# mp28164-buck-boost-flashlight-driver-17m.net
KiCad netlist of a schematic drawn in EAGLE
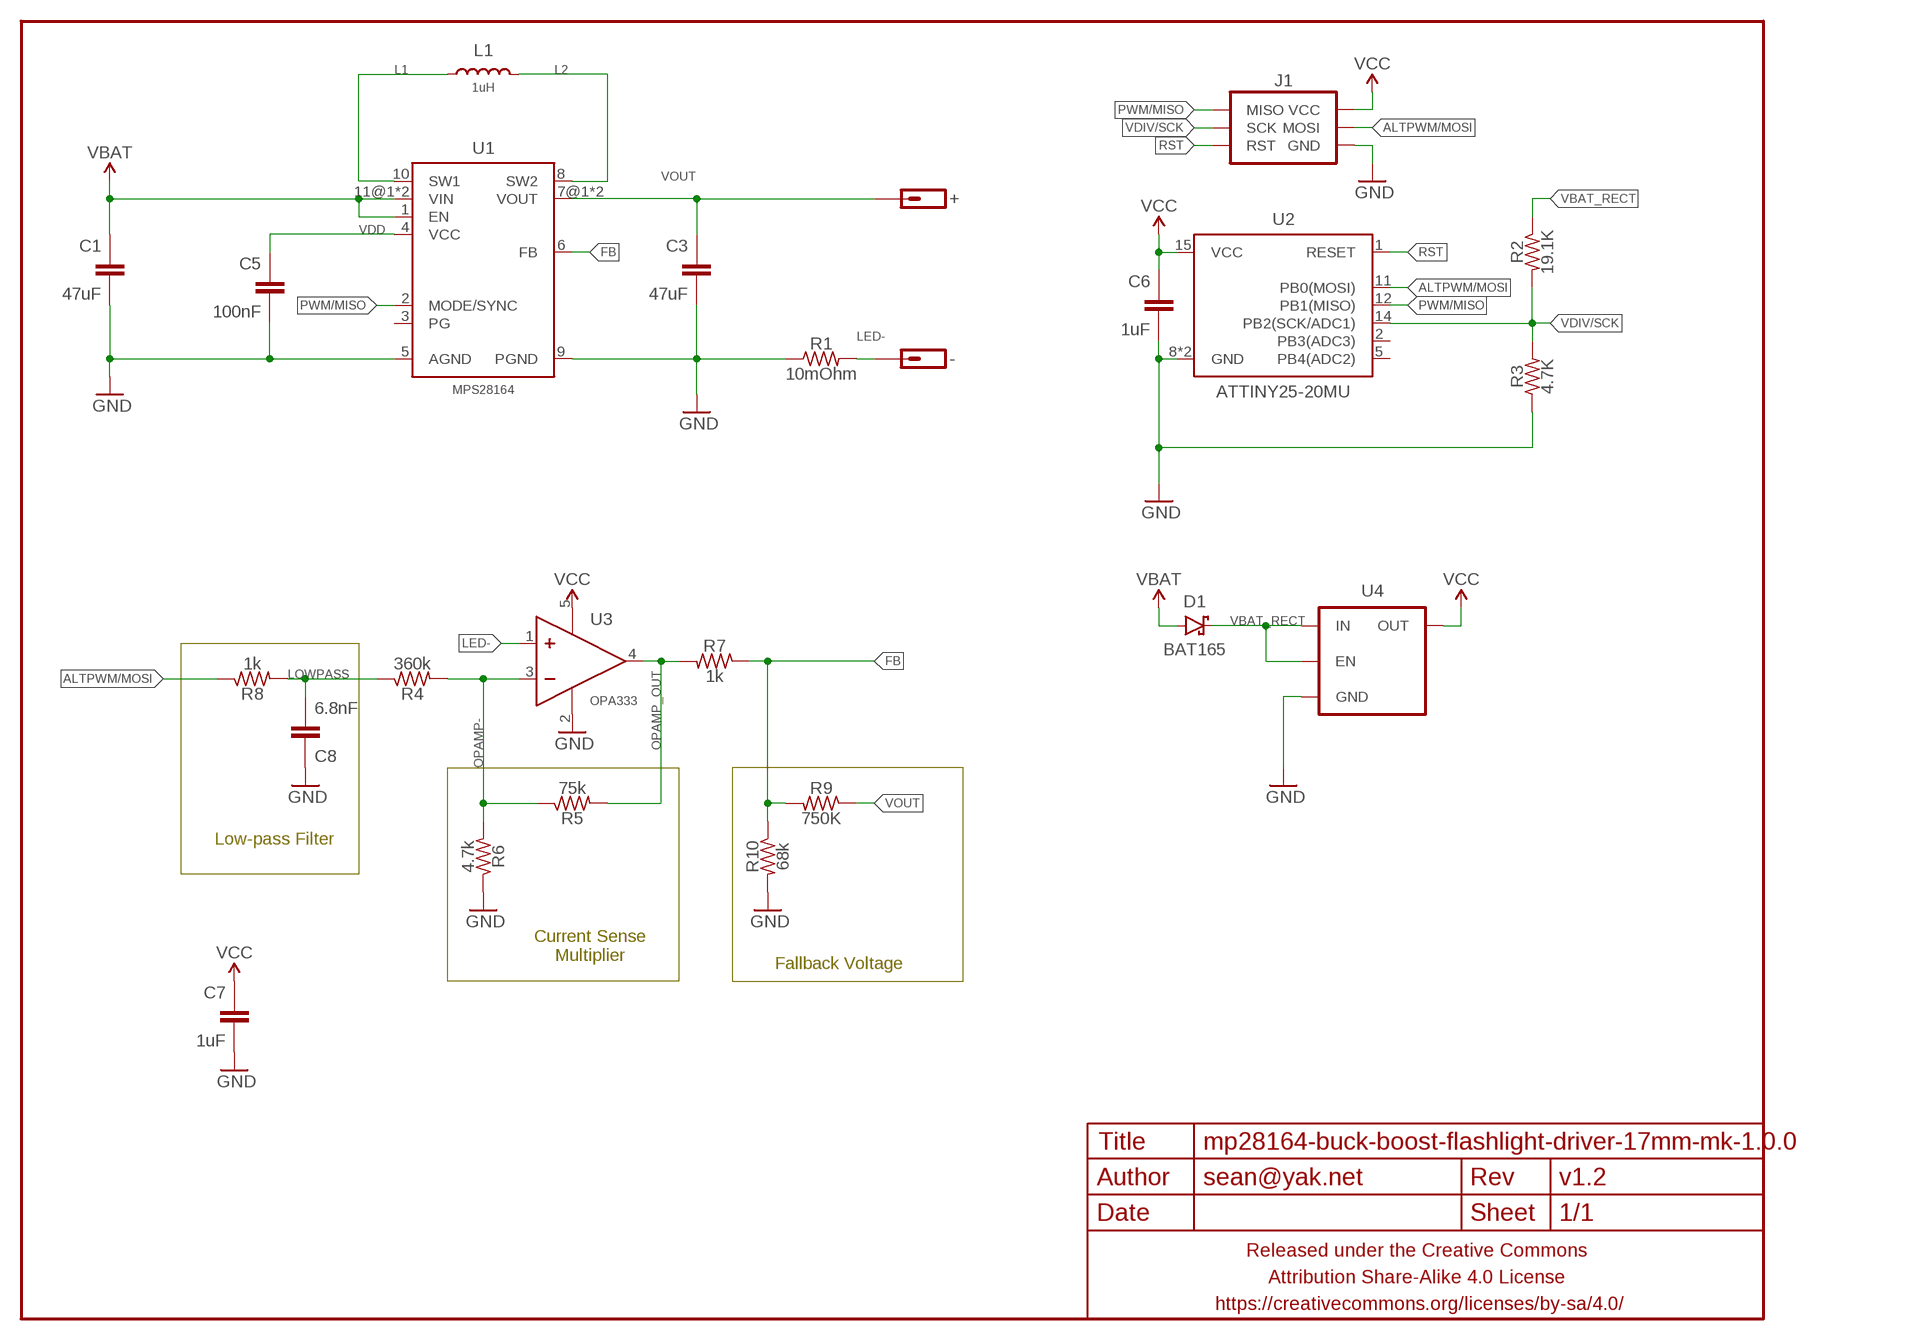
[diagram p0: schematic, sheet 1]

(export (version "E")
  (design (tool "Eeschema 10.0.6"))
  (components
    (comp (ref "+")
      (value "M01SMD-1.6MMX3.2MM-NS")
      (footprint "eagle-import:1X01-SMD-1.6MMX3.2MM-NS")
      (libsource (lib "eagle-import") (part "M01SMD-1.6MMX3.2MM-NS"))
    )
    (comp (ref "-")
      (value "M01SMD-1.6MMX3.2MM-NS")
      (footprint "eagle-import:1X01-SMD-1.6MMX3.2MM-NS")
      (libsource (lib "eagle-import") (part "M01SMD-1.6MMX3.2MM-NS"))
    )
    (comp (ref "C1")
      (value "47uF")
      (footprint "eagle-import:C1206")
      (libsource (lib "eagle-import") (part "CAPACITOR-CERAMICC1206"))
    )
    (comp (ref "C3")
      (value "47uF")
      (footprint "eagle-import:C1206")
      (libsource (lib "eagle-import") (part "CAPACITOR-CERAMICC1206"))
    )
    (comp (ref "C5")
      (value "100nF")
      (footprint "eagle-import:C0402")
      (libsource (lib "eagle-import") (part "CAPACITOR-CERAMICC0402"))
    )
    (comp (ref "C6")
      (value "1uF")
      (footprint "eagle-import:C0402")
      (libsource (lib "eagle-import") (part "CAPACITOR-CERAMICC0402"))
    )
    (comp (ref "C7")
      (value "1uF")
      (footprint "eagle-import:C0402")
      (libsource (lib "eagle-import") (part "CAPACITOR-CERAMICC0402"))
    )
    (comp (ref "C8")
      (value "6.8nF")
      (footprint "eagle-import:C0402")
      (libsource (lib "eagle-import") (part "CAPACITOR-CERAMICC0402"))
    )
    (comp (ref "D1")
      (value "BAT165")
      (footprint "eagle-import:SOD323-SCHOTTKY")
      (libsource (lib "eagle-import") (part "DIODE-SCHOTTKYSOD323"))
    )
    (comp (ref "FRAME1")
      (value "FRAME-LETTERNO_PACKAGE")
      (footprint "eagle-import:DUMMY")
      (fields
        (field (name "DESIGNER") "sean@yak.net")
        (field (name "VERSION") "v1.2")
        (field (name "DESIGNER_1") "sean@yak.net")
        (field (name "VERSION_1") "v1.2")
      )
      (libsource (lib "eagle-import") (part "FRAME-LETTERNO_PACKAGE"))
    )
    (comp (ref "J1")
      (value "AVR_SPI_PRG_6SMD-1.27MM")
      (footprint "eagle-import:2X3-1.27MM-SMD")
      (libsource (lib "eagle-import") (part "AVR_SPI_PRG_6SMD-1.27MM"))
    )
    (comp (ref "L1")
      (value "1uH")
      (footprint "eagle-import:XAL7070")
      (libsource (lib "eagle-import") (part "INDUCTORXAL7070"))
    )
    (comp (ref "R1")
      (value "10mOhm")
      (footprint "eagle-import:R0805-TIGHTER")
      (libsource (lib "eagle-import") (part "RESISTORR0805-TIGHTER"))
    )
    (comp (ref "R2")
      (value "19.1K")
      (footprint "eagle-import:R0402")
      (libsource (lib "eagle-import") (part "RESISTORR0402"))
    )
    (comp (ref "R3")
      (value "4.7K")
      (footprint "eagle-import:R0402")
      (libsource (lib "eagle-import") (part "RESISTORR0402"))
    )
    (comp (ref "R4")
      (value "360k")
      (footprint "eagle-import:R0402")
      (libsource (lib "eagle-import") (part "RESISTORR0402"))
    )
    (comp (ref "R5")
      (value "75k")
      (footprint "eagle-import:R0402")
      (libsource (lib "eagle-import") (part "RESISTORR0402"))
    )
    (comp (ref "R6")
      (value "4.7k")
      (footprint "eagle-import:R0402")
      (libsource (lib "eagle-import") (part "RESISTORR0402"))
    )
    (comp (ref "R7")
      (value "1k")
      (footprint "eagle-import:R0402")
      (libsource (lib "eagle-import") (part "RESISTORR0402"))
    )
    (comp (ref "R8")
      (value "1k")
      (footprint "eagle-import:R0402")
      (libsource (lib "eagle-import") (part "RESISTORR0402"))
    )
    (comp (ref "R9")
      (value "750K")
      (footprint "eagle-import:R0402")
      (libsource (lib "eagle-import") (part "RESISTORR0402"))
    )
    (comp (ref "R10")
      (value "68k")
      (footprint "eagle-import:R0402")
      (libsource (lib "eagle-import") (part "RESISTORR0402"))
    )
    (comp (ref "U1")
      (value "MPS28164")
      (footprint "eagle-import:MPS28164")
      (libsource (lib "eagle-import") (part "MPS28164"))
    )
    (comp (ref "U2")
      (value "ATTINY25-20MU")
      (footprint "eagle-import:QFN20")
      (libsource (lib "eagle-import") (part "ATTINY45TINY85-20-QFN"))
    )
    (comp (ref "U3")
      (value "OPA333")
      (footprint "eagle-import:SC70")
      (libsource (lib "eagle-import") (part "OPAMPOPA333-SC-70"))
    )
    (comp (ref "U4")
      (value "V_REG_ENTLV700")
      (footprint "eagle-import:SC70")
      (libsource (lib "eagle-import") (part "V_REG_ENTLV700"))
    )
  )
  (nets
    (net (code "1") (name "/L1") (class "Default")
      (node (ref "L1") (pin "P$1") (pinfunction "1_P$1") (pintype "passive"))
      (node (ref "U1") (pin "10") (pinfunction "SW1_10") (pintype "bidirectional"))
    )
    (net (code "2") (name "/L2") (class "Default")
      (node (ref "L1") (pin "P$2") (pinfunction "2_P$2") (pintype "passive"))
      (node (ref "U1") (pin "8") (pinfunction "SW2_8") (pintype "bidirectional"))
    )
    (net (code "3") (name "/LOWPASS") (class "Default")
      (node (ref "C8") (pin "2") (pinfunction "2_2") (pintype "passive"))
      (node (ref "R4") (pin "1") (pinfunction "1_1") (pintype "passive"))
      (node (ref "R8") (pin "2") (pinfunction "2_2") (pintype "passive"))
    )
    (net (code "4") (name "/OPAMP-") (class "Default")
      (node (ref "R4") (pin "2") (pinfunction "2_2") (pintype "passive"))
      (node (ref "R5") (pin "1") (pinfunction "1_1") (pintype "passive"))
      (node (ref "R6") (pin "2") (pinfunction "2_2") (pintype "passive"))
      (node (ref "U3") (pin "3") (pinfunction "IN-_3") (pintype "input"))
    )
    (net (code "5") (name "/OPAMP_OUT") (class "Default")
      (node (ref "R5") (pin "2") (pinfunction "2_2") (pintype "passive"))
      (node (ref "R7") (pin "2") (pinfunction "2_2") (pintype "passive"))
      (node (ref "U3") (pin "4") (pinfunction "OUT_4") (pintype "output"))
    )
    (net (code "6") (name "/VDD") (class "Default")
      (node (ref "C5") (pin "1") (pinfunction "1_1") (pintype "passive"))
      (node (ref "U1") (pin "4") (pinfunction "VCC_4") (pintype "bidirectional"))
    )
    (net (code "7") (name "ALTPWM{slash}MOSI") (class "Default")
      (node (ref "J1") (pin "4") (pinfunction "MOSI_4") (pintype "passive"))
      (node (ref "R8") (pin "1") (pinfunction "1_1") (pintype "passive"))
      (node (ref "U2") (pin "11") (pinfunction "PB0(MOSI)_11") (pintype "bidirectional"))
    )
    (net (code "8") (name "FB") (class "Default")
      (node (ref "R10") (pin "1") (pinfunction "1_1") (pintype "passive"))
      (node (ref "R7") (pin "1") (pinfunction "1_1") (pintype "passive"))
      (node (ref "R9") (pin "2") (pinfunction "2_2") (pintype "passive"))
      (node (ref "U1") (pin "6") (pinfunction "FB_6") (pintype "bidirectional"))
    )
    (net (code "9") (name "GND") (class "Default")
      (node (ref "C1") (pin "2") (pinfunction "2_2") (pintype "passive"))
      (node (ref "C3") (pin "2") (pinfunction "2_2") (pintype "passive"))
      (node (ref "C5") (pin "2") (pinfunction "2_2") (pintype "passive"))
      (node (ref "C6") (pin "2") (pinfunction "2_2") (pintype "passive"))
      (node (ref "C7") (pin "2") (pinfunction "2_2") (pintype "passive"))
      (node (ref "C8") (pin "1") (pinfunction "1_1") (pintype "passive"))
      (node (ref "J1") (pin "6") (pinfunction "GND_6") (pintype "passive"))
      (node (ref "R1") (pin "1") (pinfunction "1_1") (pintype "passive"))
      (node (ref "R10") (pin "2") (pinfunction "2_2") (pintype "passive"))
      (node (ref "R3") (pin "1") (pinfunction "1_1") (pintype "passive"))
      (node (ref "R6") (pin "1") (pinfunction "1_1") (pintype "passive"))
      (node (ref "U1") (pin "5") (pinfunction "AGND_5") (pintype "bidirectional"))
      (node (ref "U1") (pin "9") (pinfunction "PGND_9") (pintype "bidirectional"))
      (node (ref "U2") (pin "8") (pinfunction "GND_8") (pintype "bidirectional"))
      (node (ref "U2") (pin "PAD") (pinfunction "GND_PAD") (pintype "bidirectional"))
      (node (ref "U3") (pin "2") (pinfunction "V-_2") (pintype "power_in"))
      (node (ref "U4") (pin "2") (pinfunction "GND_2") (pintype "input"))
    )
    (net (code "10") (name "LED-") (class "Default")
      (node (ref "-") (pin "P$1") (pinfunction "1_P$1") (pintype "passive"))
      (node (ref "R1") (pin "2") (pinfunction "2_2") (pintype "passive"))
      (node (ref "U3") (pin "1") (pinfunction "IN+_1") (pintype "input"))
    )
    (net (code "11") (name "PWM{slash}MISO") (class "Default")
      (node (ref "J1") (pin "1") (pinfunction "MISO_1") (pintype "passive"))
      (node (ref "U1") (pin "2") (pinfunction "MODE/SYNC_2") (pintype "bidirectional"))
      (node (ref "U2") (pin "12") (pinfunction "PB1(MISO)_12") (pintype "bidirectional"))
    )
    (net (code "12") (name "RST") (class "Default")
      (node (ref "J1") (pin "5") (pinfunction "RST_5") (pintype "passive"))
      (node (ref "U2") (pin "1") (pinfunction "RESET_1") (pintype "bidirectional"))
    )
    (net (code "13") (name "VBAT") (class "Default")
      (node (ref "C1") (pin "1") (pinfunction "1_1") (pintype "passive"))
      (node (ref "D1") (pin "A") (pinfunction "A_A") (pintype "passive"))
      (node (ref "U1") (pin "1") (pinfunction "EN_1") (pintype "bidirectional"))
      (node (ref "U1") (pin "11@1") (pinfunction "VIN_11@1") (pintype "bidirectional"))
      (node (ref "U1") (pin "11@2") (pinfunction "VIN_11@2") (pintype "bidirectional"))
    )
    (net (code "14") (name "VBAT_RECT") (class "Default")
      (node (ref "D1") (pin "C") (pinfunction "C_C") (pintype "passive"))
      (node (ref "R2") (pin "1") (pinfunction "1_1") (pintype "passive"))
      (node (ref "U4") (pin "1") (pinfunction "IN_1") (pintype "input"))
      (node (ref "U4") (pin "3") (pinfunction "EN_3") (pintype "input"))
    )
    (net (code "15") (name "VCC") (class "Default")
      (node (ref "C6") (pin "1") (pinfunction "1_1") (pintype "passive"))
      (node (ref "C7") (pin "1") (pinfunction "1_1") (pintype "passive"))
      (node (ref "J1") (pin "2") (pinfunction "VCC_2") (pintype "passive"))
      (node (ref "U2") (pin "15") (pinfunction "VCC_15") (pintype "bidirectional"))
      (node (ref "U3") (pin "5") (pinfunction "V+_5") (pintype "power_in"))
      (node (ref "U4") (pin "5") (pinfunction "OUT_5") (pintype "passive"))
    )
    (net (code "16") (name "VDIV{slash}SCK") (class "Default")
      (node (ref "J1") (pin "3") (pinfunction "SCK_3") (pintype "passive"))
      (node (ref "R2") (pin "2") (pinfunction "2_2") (pintype "passive"))
      (node (ref "R3") (pin "2") (pinfunction "2_2") (pintype "passive"))
      (node (ref "U2") (pin "14") (pinfunction "PB2(SCK/ADC1)_14") (pintype "bidirectional"))
    )
    (net (code "17") (name "VOUT") (class "Default")
      (node (ref "+") (pin "P$1") (pinfunction "1_P$1") (pintype "passive"))
      (node (ref "C3") (pin "1") (pinfunction "1_1") (pintype "passive"))
      (node (ref "R9") (pin "1") (pinfunction "1_1") (pintype "passive"))
      (node (ref "U1") (pin "7@1") (pinfunction "VOUT_7@1") (pintype "bidirectional"))
      (node (ref "U1") (pin "7@2") (pinfunction "VOUT_7@2") (pintype "bidirectional"))
    )
    (net (code "18") (name "unconnected-(U1-PG-Pad3)") (class "Default")
      (node (ref "U1") (pin "3") (pinfunction "PG_3") (pintype "bidirectional"))
    )
    (net (code "19") (name "unconnected-(U2-PB3(ADC3)-Pad2)") (class "Default")
      (node (ref "U2") (pin "2") (pinfunction "PB3(ADC3)_2") (pintype "bidirectional"))
    )
    (net (code "20") (name "unconnected-(U2-PB4(ADC2)-Pad5)") (class "Default")
      (node (ref "U2") (pin "5") (pinfunction "PB4(ADC2)_5") (pintype "bidirectional"))
    )
  )
)
